# deepak_sch_Newest.net
KiCad netlist of a schematic drawn in EAGLE
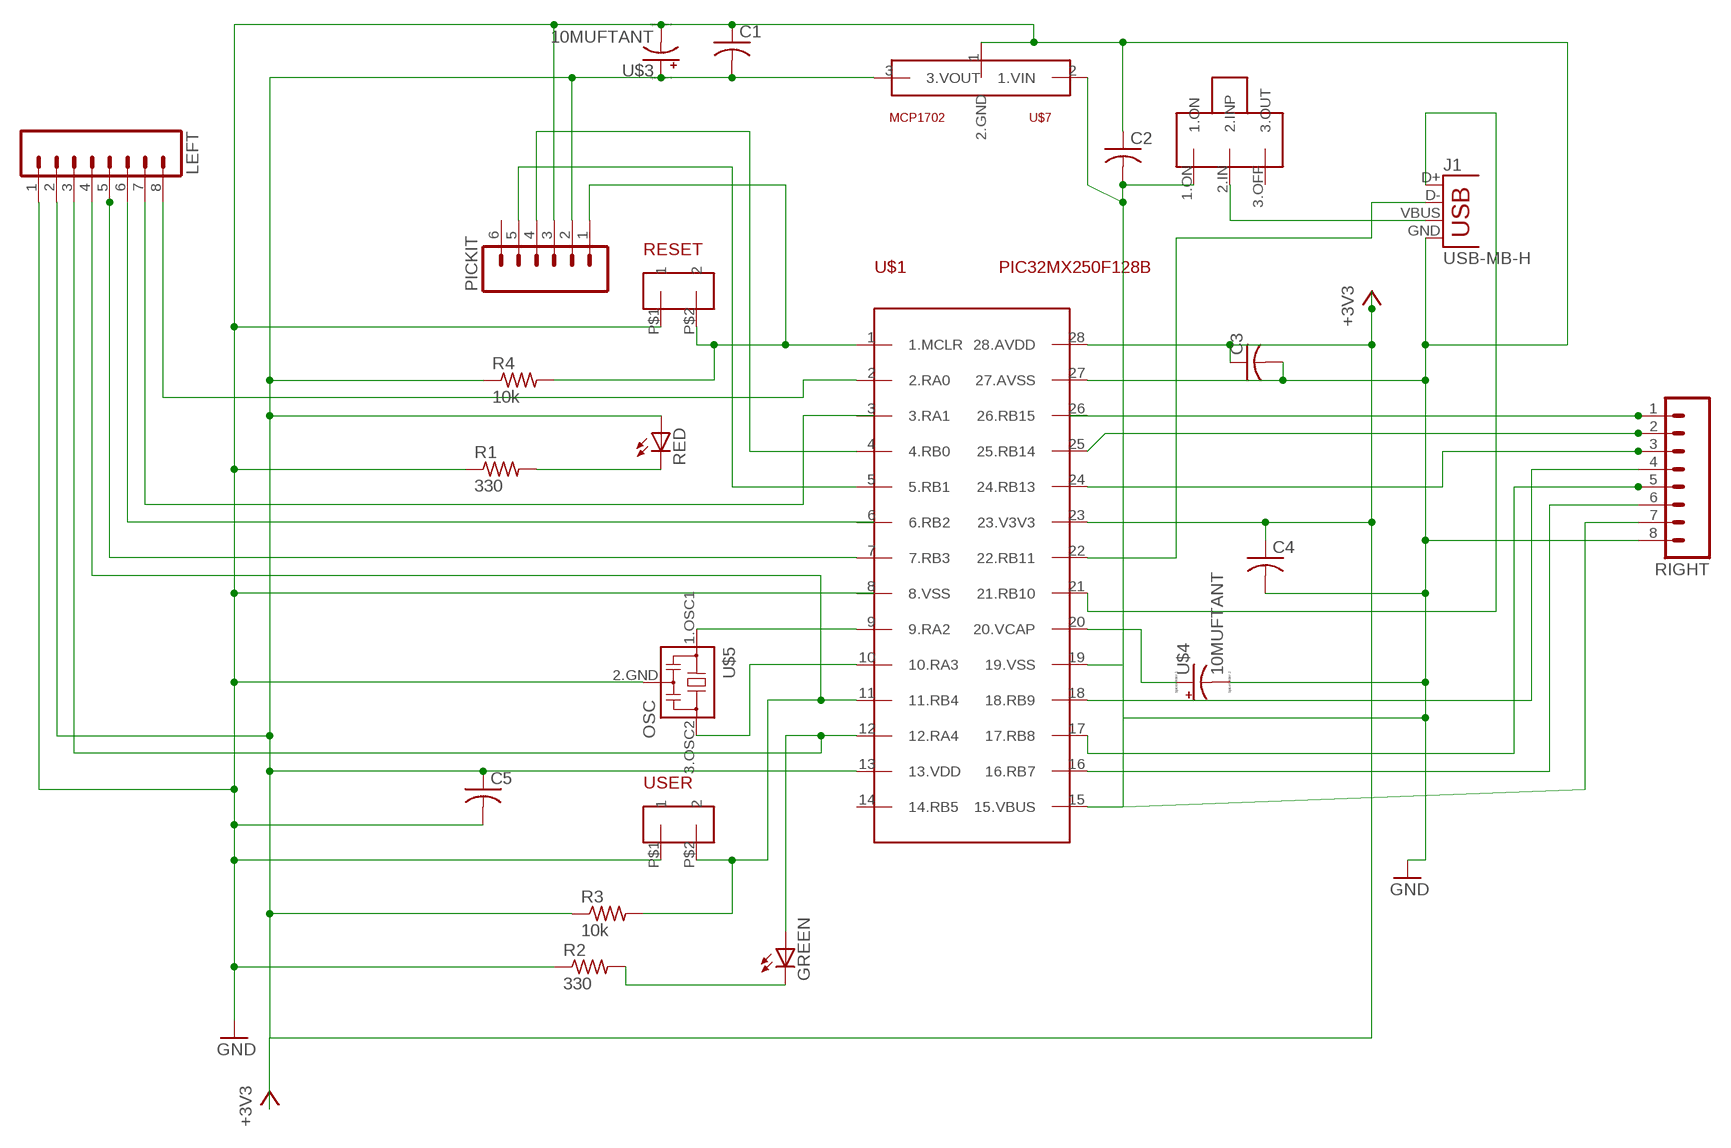
[diagram p0: schematic, sheet 1]

(export (version "E")
  (design (tool "Eeschema 10.0.6"))
  (components
    (comp (ref "C1")
      (value "C-US025-025X050")
      (footprint "eagle-import:C025-025X050")
      (libsource (lib "eagle-import") (part "C-US025-025X050"))
    )
    (comp (ref "C2")
      (value "C-US025-025X050")
      (footprint "eagle-import:C025-025X050")
      (libsource (lib "eagle-import") (part "C-US025-025X050"))
    )
    (comp (ref "C3")
      (value "C-US025-025X050")
      (footprint "eagle-import:C025-025X050")
      (libsource (lib "eagle-import") (part "C-US025-025X050"))
    )
    (comp (ref "C4")
      (value "C-US025-025X050")
      (footprint "eagle-import:C025-025X050")
      (libsource (lib "eagle-import") (part "C-US025-025X050"))
    )
    (comp (ref "C5")
      (value "C-US025-025X050")
      (footprint "eagle-import:C025-025X050")
      (libsource (lib "eagle-import") (part "C-US025-025X050"))
    )
    (comp (ref "GREEN")
      (value "LED3MM")
      (footprint "eagle-import:LED3MM")
      (libsource (lib "eagle-import") (part "LED3MM"))
    )
    (comp (ref "J1")
      (value "USB-MB-H")
      (footprint "eagle-import:USB-MB-H")
      (libsource (lib "eagle-import") (part "USB-MB-H"))
    )
    (comp (ref "LEFT")
      (value "M08")
      (footprint "eagle-import:1X08_ROUND")
      (libsource (lib "eagle-import") (part "M08"))
    )
    (comp (ref "PICKIT")
      (value "M06SILK_FEMALE_PTH")
      (footprint "eagle-import:1X06")
      (libsource (lib "eagle-import") (part "M06SILK_FEMALE_PTH"))
    )
    (comp (ref "R1")
      (value "330")
      (footprint "eagle-import:0207_10")
      (libsource (lib "eagle-import") (part "R-US_0207/10"))
    )
    (comp (ref "R2")
      (value "330")
      (footprint "eagle-import:0207_10")
      (libsource (lib "eagle-import") (part "R-US_0207/10"))
    )
    (comp (ref "R3")
      (value "10k")
      (footprint "eagle-import:0207_10")
      (libsource (lib "eagle-import") (part "R-US_0207/10"))
    )
    (comp (ref "R4")
      (value "10k")
      (footprint "eagle-import:0207_10")
      (libsource (lib "eagle-import") (part "R-US_0207/10"))
    )
    (comp (ref "RED")
      (value "LED3MM")
      (footprint "eagle-import:LED3MM")
      (libsource (lib "eagle-import") (part "LED3MM"))
    )
    (comp (ref "RESET")
      (value "PUSHBTN")
      (footprint "eagle-import:PUSHBTN")
      (libsource (lib "eagle-import") (part "PUSHBTN"))
    )
    (comp (ref "RIGHT")
      (value "M08")
      (footprint "eagle-import:1X08_ROUND")
      (libsource (lib "eagle-import") (part "M08"))
    )
    (comp (ref "U$1")
      (value "PIC32MX250F128B")
      (footprint "eagle-import:DIL28-3")
      (libsource (lib "eagle-import") (part "PIC32MX250F128B"))
    )
    (comp (ref "U$2")
      (value "SLIDESWITCH")
      (footprint "eagle-import:SLIDESWITCH")
      (libsource (lib "eagle-import") (part "SLIDESWITCH"))
    )
    (comp (ref "U$3")
      (value "10MUFTANT")
      (footprint "eagle-import:10MUFTANT")
      (libsource (lib "eagle-import") (part "10MUFTANT"))
    )
    (comp (ref "U$4")
      (value "10MUFTANT")
      (footprint "eagle-import:10MUFTANT")
      (libsource (lib "eagle-import") (part "10MUFTANT"))
    )
    (comp (ref "U$5")
      (value "OSC")
      (footprint "eagle-import:OSC")
      (libsource (lib "eagle-import") (part "OSC"))
    )
    (comp (ref "U$7")
      (value "MCP1702")
      (footprint "eagle-import:TO92")
      (libsource (lib "eagle-import") (part "MCP1702"))
    )
    (comp (ref "USER")
      (value "PUSHBTN")
      (footprint "eagle-import:PUSHBTN")
      (libsource (lib "eagle-import") (part "PUSHBTN"))
    )
  )
  (nets
    (net (code "1") (name "+3V3") (class "Default")
      (node (ref "C1") (pin "2") (pinfunction "2_2") (pintype "passive"))
      (node (ref "C3") (pin "1") (pinfunction "1_1") (pintype "passive"))
      (node (ref "C4") (pin "1") (pinfunction "1_1") (pintype "passive"))
      (node (ref "C5") (pin "1") (pinfunction "1_1") (pintype "passive"))
      (node (ref "LEFT") (pin "2") (pinfunction "2_2") (pintype "passive"))
      (node (ref "PICKIT") (pin "2") (pinfunction "2_2") (pintype "passive"))
      (node (ref "R3") (pin "1") (pinfunction "1_1") (pintype "passive"))
      (node (ref "R4") (pin "1") (pinfunction "1_1") (pintype "passive"))
      (node (ref "RED") (pin "A") (pinfunction "A_A") (pintype "passive"))
      (node (ref "U$1") (pin "13") (pinfunction "13.VDD_13") (pintype "bidirectional"))
      (node (ref "U$1") (pin "23") (pinfunction "23.V3V3_23") (pintype "bidirectional"))
      (node (ref "U$1") (pin "28") (pinfunction "28.AVDD_28") (pintype "bidirectional"))
      (node (ref "U$3") (pin "1.PLUS") (pinfunction "+_1.PLUS") (pintype "passive"))
      (node (ref "U$7") (pin "3") (pinfunction "3.VOUT_3") (pintype "bidirectional"))
    )
    (net (code "2") (name "GND") (class "Default")
      (node (ref "C1") (pin "1") (pinfunction "1_1") (pintype "passive"))
      (node (ref "C2") (pin "1") (pinfunction "1_1") (pintype "passive"))
      (node (ref "C3") (pin "2") (pinfunction "2_2") (pintype "passive"))
      (node (ref "C4") (pin "2") (pinfunction "2_2") (pintype "passive"))
      (node (ref "C5") (pin "2") (pinfunction "2_2") (pintype "passive"))
      (node (ref "J1") (pin "GND") (pinfunction "GND_GND") (pintype "bidirectional"))
      (node (ref "LEFT") (pin "1") (pinfunction "1_1") (pintype "passive"))
      (node (ref "PICKIT") (pin "3") (pinfunction "3_3") (pintype "passive"))
      (node (ref "R1") (pin "1") (pinfunction "1_1") (pintype "passive"))
      (node (ref "R2") (pin "1") (pinfunction "1_1") (pintype "passive"))
      (node (ref "RESET") (pin "P$1") (pinfunction "1_P$1") (pintype "bidirectional"))
      (node (ref "RIGHT") (pin "8") (pinfunction "8_8") (pintype "passive"))
      (node (ref "U$1") (pin "19") (pinfunction "19.VSS_19") (pintype "bidirectional"))
      (node (ref "U$1") (pin "27") (pinfunction "27.AVSS_27") (pintype "bidirectional"))
      (node (ref "U$3") (pin "2.MINUS") (pinfunction "-_2.MINUS") (pintype "passive"))
      (node (ref "U$4") (pin "2.MINUS") (pinfunction "-_2.MINUS") (pintype "passive"))
      (node (ref "U$5") (pin "2.GND") (pinfunction "2_2.GND") (pintype "passive"))
      (node (ref "U$7") (pin "1") (pinfunction "2.GND_1") (pintype "bidirectional"))
      (node (ref "USER") (pin "P$1") (pinfunction "1_P$1") (pintype "bidirectional"))
    )
    (net (code "3") (name "Net-(GREEN-C)") (class "Default")
      (node (ref "GREEN") (pin "K") (pinfunction "C_K") (pintype "passive"))
      (node (ref "R2") (pin "2") (pinfunction "2_2") (pintype "passive"))
    )
    (net (code "4") (name "Net-(RED-C)") (class "Default")
      (node (ref "R1") (pin "2") (pinfunction "2_2") (pintype "passive"))
      (node (ref "RED") (pin "K") (pinfunction "C_K") (pintype "passive"))
    )
    (net (code "5") (name "Net-(RESET-2)") (class "Default")
      (node (ref "PICKIT") (pin "1") (pinfunction "1_1") (pintype "passive"))
      (node (ref "R4") (pin "2") (pinfunction "2_2") (pintype "passive"))
      (node (ref "RESET") (pin "P$2") (pinfunction "2_P$2") (pintype "bidirectional"))
      (node (ref "U$1") (pin "1") (pinfunction "1.MCLR_1") (pintype "bidirectional"))
    )
    (net (code "6") (name "Net-(U$1-2.RA0)") (class "Default")
      (node (ref "LEFT") (pin "8") (pinfunction "8_8") (pintype "passive"))
      (node (ref "U$1") (pin "2") (pinfunction "2.RA0_2") (pintype "bidirectional"))
    )
    (net (code "7") (name "Net-(U$1-4.RB0)") (class "Default")
      (node (ref "PICKIT") (pin "4") (pinfunction "4_4") (pintype "passive"))
      (node (ref "U$1") (pin "4") (pinfunction "4.RB0_4") (pintype "bidirectional"))
    )
    (net (code "8") (name "Net-(U$1-5.RB1)") (class "Default")
      (node (ref "PICKIT") (pin "5") (pinfunction "5_5") (pintype "passive"))
      (node (ref "U$1") (pin "5") (pinfunction "5.RB1_5") (pintype "bidirectional"))
    )
    (net (code "9") (name "Net-(U$1-7.RB3)") (class "Default")
      (node (ref "LEFT") (pin "5") (pinfunction "5_5") (pintype "passive"))
      (node (ref "U$1") (pin "7") (pinfunction "7.RB3_7") (pintype "bidirectional"))
    )
    (net (code "10") (name "Net-(U$1-9.RA2)") (class "Default")
      (node (ref "U$1") (pin "9") (pinfunction "9.RA2_9") (pintype "bidirectional"))
      (node (ref "U$5") (pin "1.OSC1") (pinfunction "1_1.OSC1") (pintype "passive"))
    )
    (net (code "11") (name "Net-(U$1-10.RA3)") (class "Default")
      (node (ref "U$1") (pin "10") (pinfunction "10.RA3_10") (pintype "bidirectional"))
      (node (ref "U$5") (pin "3.OSC2") (pinfunction "3_3.OSC2") (pintype "passive"))
    )
    (net (code "12") (name "Net-(U$1-11.RB4)") (class "Default")
      (node (ref "LEFT") (pin "4") (pinfunction "4_4") (pintype "passive"))
      (node (ref "R3") (pin "2") (pinfunction "2_2") (pintype "passive"))
      (node (ref "U$1") (pin "11") (pinfunction "11.RB4_11") (pintype "bidirectional"))
      (node (ref "USER") (pin "P$2") (pinfunction "2_P$2") (pintype "bidirectional"))
    )
    (net (code "13") (name "Net-(U$1-12.RA4)") (class "Default")
      (node (ref "GREEN") (pin "A") (pinfunction "A_A") (pintype "passive"))
      (node (ref "LEFT") (pin "3") (pinfunction "3_3") (pintype "passive"))
      (node (ref "U$1") (pin "12") (pinfunction "12.RA4_12") (pintype "bidirectional"))
    )
    (net (code "14") (name "Net-(U$1-15.VBUS)") (class "Default")
      (node (ref "C2") (pin "2") (pinfunction "2_2") (pintype "passive"))
      (node (ref "RIGHT") (pin "7") (pinfunction "7_7") (pintype "passive"))
      (node (ref "U$1") (pin "15") (pinfunction "15.VBUS_15") (pintype "bidirectional"))
      (node (ref "U$2") (pin "1.ON") (pinfunction "1.ON_1.ON") (pintype "bidirectional"))
      (node (ref "U$7") (pin "2") (pinfunction "1.VIN_2") (pintype "bidirectional"))
    )
    (net (code "15") (name "Net-(U$1-16.RB7)") (class "Default")
      (node (ref "RIGHT") (pin "6") (pinfunction "6_6") (pintype "passive"))
      (node (ref "U$1") (pin "16") (pinfunction "16.RB7_16") (pintype "bidirectional"))
    )
    (net (code "16") (name "Net-(U$1-17.RB8)") (class "Default")
      (node (ref "RIGHT") (pin "5") (pinfunction "5_5") (pintype "passive"))
      (node (ref "U$1") (pin "17") (pinfunction "17.RB8_17") (pintype "bidirectional"))
    )
    (net (code "17") (name "Net-(U$1-18.RB9)") (class "Default")
      (node (ref "RIGHT") (pin "4") (pinfunction "4_4") (pintype "passive"))
      (node (ref "U$1") (pin "18") (pinfunction "18.RB9_18") (pintype "bidirectional"))
    )
    (net (code "18") (name "Net-(U$1-20.VCAP)") (class "Default")
      (node (ref "U$1") (pin "20") (pinfunction "20.VCAP_20") (pintype "bidirectional"))
      (node (ref "U$4") (pin "1.PLUS") (pinfunction "+_1.PLUS") (pintype "passive"))
    )
    (net (code "19") (name "Net-(U$1-21.RB10)") (class "Default")
      (node (ref "J1") (pin "D+") (pinfunction "D+_D+") (pintype "bidirectional"))
      (node (ref "U$1") (pin "21") (pinfunction "21.RB10_21") (pintype "bidirectional"))
    )
    (net (code "20") (name "Net-(U$1-22.RB11)") (class "Default")
      (node (ref "J1") (pin "D-") (pinfunction "D-_D-") (pintype "bidirectional"))
      (node (ref "U$1") (pin "22") (pinfunction "22.RB11_22") (pintype "bidirectional"))
    )
    (net (code "21") (name "Net-(U$1-24.RB13)") (class "Default")
      (node (ref "RIGHT") (pin "3") (pinfunction "3_3") (pintype "passive"))
      (node (ref "U$1") (pin "24") (pinfunction "24.RB13_24") (pintype "bidirectional"))
    )
    (net (code "22") (name "Net-(U$1-25.RB14)") (class "Default")
      (node (ref "RIGHT") (pin "2") (pinfunction "2_2") (pintype "passive"))
      (node (ref "U$1") (pin "25") (pinfunction "25.RB14_25") (pintype "bidirectional"))
    )
    (net (code "23") (name "Net-(U$2-2.INP)") (class "Default")
      (node (ref "J1") (pin "VBUS") (pinfunction "VBUS_VBUS") (pintype "bidirectional"))
      (node (ref "U$2") (pin "2.IN") (pinfunction "2.INP_2.IN") (pintype "bidirectional"))
    )
    (net (code "24") (name "unconnected-(LEFT-Pad6)") (class "Default")
      (node (ref "LEFT") (pin "6") (pinfunction "6_6") (pintype "passive"))
    )
    (net (code "25") (name "unconnected-(LEFT-Pad7)") (class "Default")
      (node (ref "LEFT") (pin "7") (pinfunction "7_7") (pintype "passive"))
    )
    (net (code "26") (name "unconnected-(PICKIT-Pad6)") (class "Default")
      (node (ref "PICKIT") (pin "6") (pinfunction "6_6") (pintype "passive"))
    )
    (net (code "27") (name "unconnected-(RIGHT-Pad1)") (class "Default")
      (node (ref "RIGHT") (pin "1") (pinfunction "1_1") (pintype "passive"))
    )
    (net (code "28") (name "unconnected-(U$1-3.RA1-Pad3)") (class "Default")
      (node (ref "U$1") (pin "3") (pinfunction "3.RA1_3") (pintype "bidirectional"))
    )
    (net (code "29") (name "unconnected-(U$1-6.RB2-Pad6)") (class "Default")
      (node (ref "U$1") (pin "6") (pinfunction "6.RB2_6") (pintype "bidirectional"))
    )
    (net (code "30") (name "unconnected-(U$1-8.VSS-Pad8)") (class "Default")
      (node (ref "U$1") (pin "8") (pinfunction "8.VSS_8") (pintype "bidirectional"))
    )
    (net (code "31") (name "unconnected-(U$1-14.RB5-Pad14)") (class "Default")
      (node (ref "U$1") (pin "14") (pinfunction "14.RB5_14") (pintype "bidirectional"))
    )
    (net (code "32") (name "unconnected-(U$1-26.RB15-Pad26)") (class "Default")
      (node (ref "U$1") (pin "26") (pinfunction "26.RB15_26") (pintype "bidirectional"))
    )
    (net (code "33") (name "unconnected-(U$2-3.OUT-Pad3.OFF)") (class "Default")
      (node (ref "U$2") (pin "3.OFF") (pinfunction "3.OUT_3.OFF") (pintype "bidirectional"))
    )
  )
)
